# STB_eFuse.net
KiCad netlist of a schematic drawn in Altium Designer
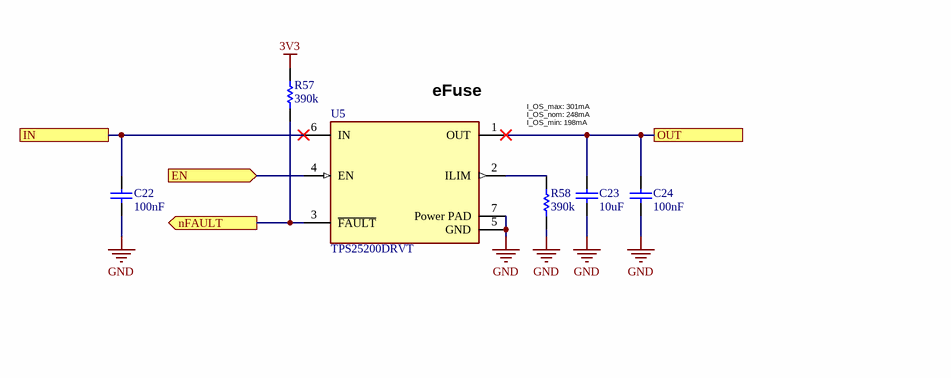
[diagram p0: STB_eFuse.SchDoc]

(export (version "E")
  (design (tool "Eeschema 10.0.6"))
  (components
    (comp (ref "C22")
      (value "100nF")
      (footprint "CAPC1050X55X23LL05T13")
      (description "Chip Capacitor, 100 nF, +/- 10%, 16 V, -55 to 125 degC, 0402 (1005 Metric), RoHS, Tape and Reel")
      (fields
        (field (name "MANUFACTURER") "Samsung Electro-Mechanics")
        (field (name "MANUFACTURER PART NUMBER") "CL05B104KO5NNNC")
      )
      (libsource (lib "Altium Content Vault") (part "CAP-NP-2"))
    )
    (comp (ref "C23")
      (value "10uF")
      (footprint "CAPC0603(1608)100_L")
      (description "CAP 10uF 10V ±10% 0603 (1608 Metric) Thickness 1mm SMD")
      (fields (field (name "TOLERANCE") "Â±10%") (field (name "MANUFACTURER") "Samsung"))
      (libsource (lib "Altium Content Vault") (part "CMP-1035-02799-1"))
    )
    (comp (ref "C24")
      (value "100nF")
      (footprint "CAPC1050X55X23LL05T13")
      (description "Chip Capacitor, 100 nF, +/- 10%, 16 V, -55 to 125 degC, 0402 (1005 Metric), RoHS, Tape and Reel")
      (fields
        (field (name "MANUFACTURER") "Samsung Electro-Mechanics")
        (field (name "MANUFACTURER PART NUMBER") "CL05B104KO5NNNC")
      )
      (libsource (lib "Altium Content Vault") (part "CAP-NP-2"))
    )
    (comp (ref "R57")
      (value "390k")
      (footprint "RESC1005X40X25LL05T05")
      (fields
        (field (name "PART NUMBER") "ERJ2RKF3903X")
        (field (name "MANUFACTURER") "Panasonic")
        (field (name "MANUFACTURER PART NUMBER") "ERJ-2RKF3903X")
      )
      (libsource (lib "Altium Content Vault") (part "RES"))
    )
    (comp (ref "R58")
      (value "390k")
      (footprint "RESC1005X40X25LL05T05")
      (fields
        (field (name "PART NUMBER") "ERJ2RKF3903X")
        (field (name "MANUFACTURER") "Panasonic")
        (field (name "MANUFACTURER PART NUMBER") "ERJ-2RKF3903X")
      )
      (libsource (lib "Altium Content Vault") (part "RES"))
    )
    (comp (ref "U5")
      (value "TPS25200DRVT")
      (footprint "FP-DRV0006A-MFG")
      (description "IC PWR MGR EFUSE 6.5V 2.8A 6SON")
      (fields (field (name "VOLTAGE") "6.5V") (field (name "MANUFACTURER") "Texas Instruments"))
      (libsource (lib "Altium Content Vault") (part "c371350b44384884d2a4ba1f5a1984b"))
    )
  )
  (nets
    (net (code "1") (name "/EN") (class "Default")
      (node (ref "U5") (pin "4") (pinfunction "EN_4") (pintype "input"))
    )
    (net (code "2") (name "/IN") (class "Default")
      (node (ref "C22") (pin "2") (pinfunction "2_2") (pintype "passive"))
      (node (ref "U5") (pin "6") (pinfunction "IN_6") (pintype "open_emitter"))
    )
    (net (code "3") (name "/OUT") (class "Default")
      (node (ref "C23") (pin "2") (pinfunction "2_2") (pintype "passive"))
      (node (ref "C24") (pin "2") (pinfunction "2_2") (pintype "passive"))
      (node (ref "U5") (pin "1") (pinfunction "OUT_1") (pintype "power_in"))
    )
    (net (code "4") (name "/nFAULT") (class "Default")
      (node (ref "R57") (pin "1") (pinfunction "1_1") (pintype "passive"))
      (node (ref "U5") (pin "3") (pinfunction "~{FAULT}_3") (pintype "open_collector"))
    )
    (net (code "5") (name "3V3") (class "Default")
      (node (ref "R57") (pin "2") (pinfunction "2_2") (pintype "passive"))
    )
    (net (code "6") (name "GND") (class "Default")
      (node (ref "C22") (pin "1") (pinfunction "1_1") (pintype "passive"))
      (node (ref "C23") (pin "1") (pinfunction "1_1") (pintype "passive"))
      (node (ref "C24") (pin "1") (pinfunction "1_1") (pintype "passive"))
      (node (ref "R58") (pin "1") (pinfunction "1_1") (pintype "passive"))
      (node (ref "U5") (pin "5") (pinfunction "GND_5") (pintype "power_in"))
      (node (ref "U5") (pin "7") (pinfunction "Power_PAD_7") (pintype "power_in"))
    )
    (net (code "7") (name "Net-(U5-ILIM)") (class "Default")
      (node (ref "R58") (pin "2") (pinfunction "2_2") (pintype "passive"))
      (node (ref "U5") (pin "2") (pinfunction "ILIM_2") (pintype "output"))
    )
  )
)
